# SCH_protopanda_v10.net
KiCad netlist of a schematic drawn in EasyEDA
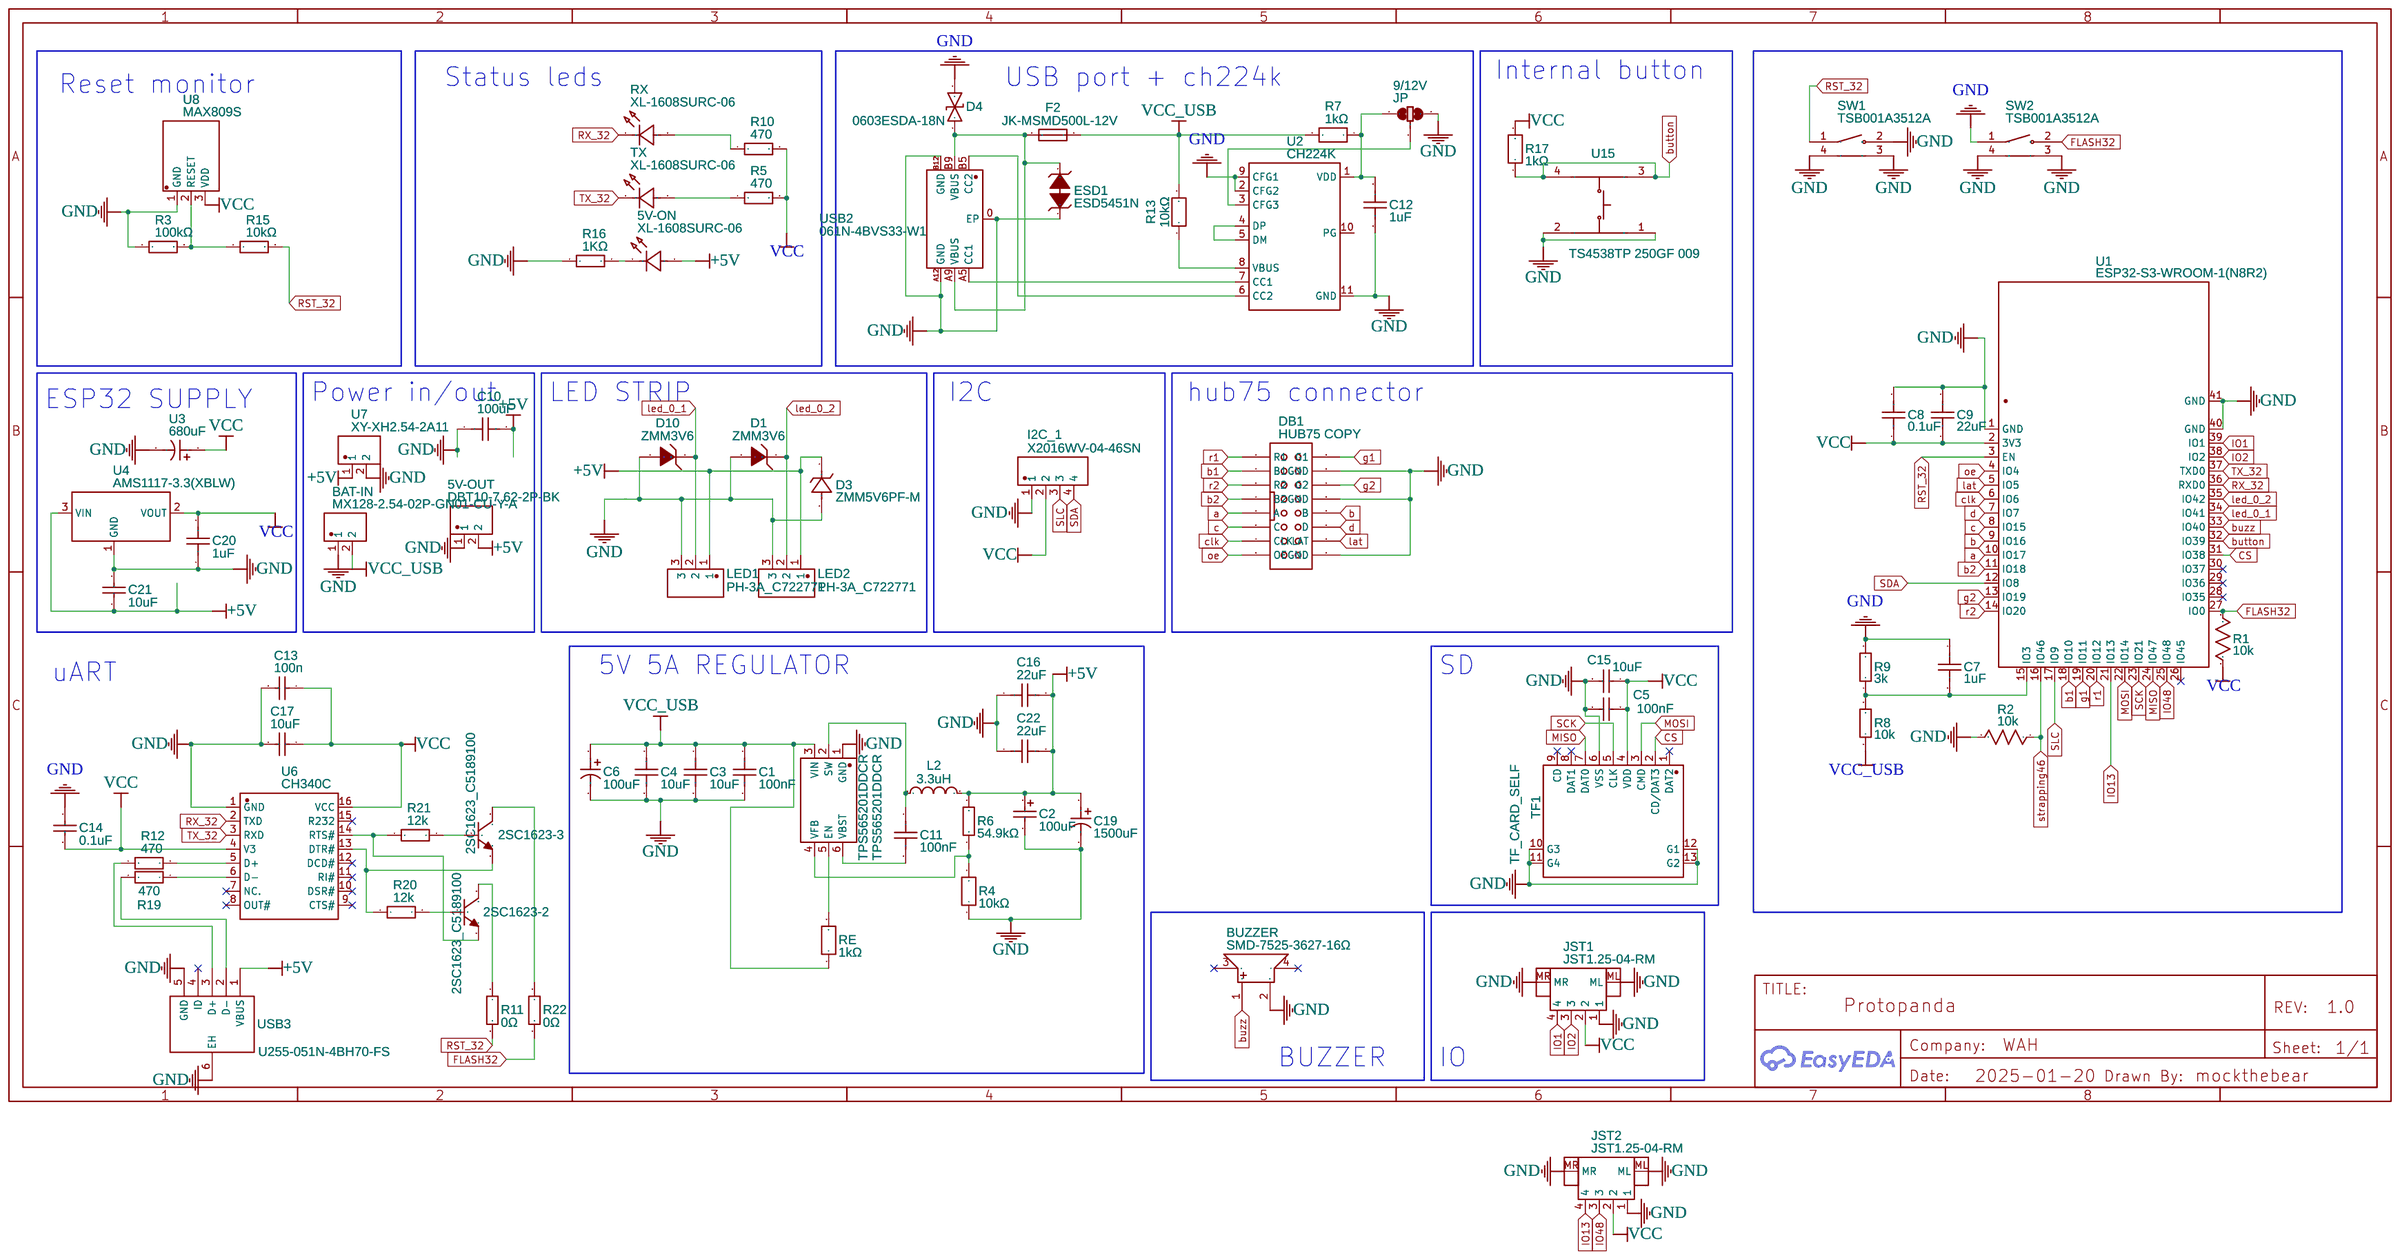
[diagram p0: schematic sheet]

(export (version "E")
  (design (tool "Eeschema 10.0.6"))
  (components
    (comp (ref "2SC1623-2")
      (value "2SC1623_C5189100")
      (fields (field (name "Manufacturer Part") "2SC1623") (field (name "Manufacturer") "HXY MOSFET(华轩阳电子)"))
      (libsource (lib "") (part "2SC1623_C5189100"))
    )
    (comp (ref "2SC1623-3")
      (value "2SC1623_C5189100")
      (fields (field (name "Manufacturer Part") "2SC1623") (field (name "Manufacturer") "HXY MOSFET(华轩阳电子)"))
      (libsource (lib "") (part "2SC1623_C5189100"))
    )
    (comp (ref "5V-ON")
      (value "XL-1608SURC-06")
      (fields (field (name "Manufacturer") "XINGLIGHT(成兴光)"))
      (libsource (lib "") (part "XL-1608SURC-06_2"))
    )
    (comp (ref "5V-OUT")
      (value "DBT10-7.62-2P-BK")
      (fields
        (field (name "Manufacturer Part") "DBT10-7.62-2P-BK-P")
        (field (name "Manufacturer") "DIBO(地博电气)")
      )
      (libsource (lib "") (part "DBT10-7.62-2P-BK"))
    )
    (comp (ref "9/12V") (value "JP") (libsource (lib "") (part "JUMPER-PAD-3-NOFULL_BOX_SILK")))
    (comp (ref "BAT-IN")
      (value "MX128-2.54-02P-GN01-CU-Y-A")
      (fields
        (field (name "Manufacturer Part") "MX128-2.54-02P-GN01-Cu-Y-A")
        (field (name "Manufacturer") "MAX(迈旭)")
      )
      (libsource (lib "") (part "MX128-2.54-02P-GN01-CU-Y-A"))
    )
    (comp (ref "BUZZER")
      (value "SMD-7525-3627-16Ω")
      (fields (field (name "Manufacturer") "S&S(海旭)"))
      (libsource (lib "") (part "SMD-7525-3627-16Ω"))
    )
    (comp (ref "C1")
      (value "100nF")
      (fields (field (name "Manufacturer Part") "CC0603CRNPO9BN5R1") (field (name "Manufacturer") "YAGEO"))
      (libsource (lib "") (part "CC0603CRNPO9BN5R1"))
    )
    (comp (ref "C2")
      (value "100uF")
      (fields
        (field (name "Manufacturer Part") "T490A107M006ATE800")
        (field (name "Manufacturer") "KEMET(基美)")
      )
      (libsource (lib "") (part "T490A107M006ATE800"))
    )
    (comp (ref "C3")
      (value "10uF")
      (fields (field (name "Manufacturer Part") "CC0603CRNPO9BN5R1") (field (name "Manufacturer") "YAGEO"))
      (libsource (lib "") (part "CC0603CRNPO9BN5R1"))
    )
    (comp (ref "C4")
      (value "10uF")
      (fields (field (name "Manufacturer Part") "CC0603CRNPO9BN5R1") (field (name "Manufacturer") "YAGEO"))
      (libsource (lib "") (part "CC0603CRNPO9BN5R1"))
    )
    (comp (ref "C5")
      (value "100nF")
      (fields (field (name "Manufacturer Part") "C0603X104K101T") (field (name "Manufacturer") "HEC"))
      (libsource (lib "") (part "C0603X104K101T"))
    )
    (comp (ref "C6")
      (value "100uF")
      (fields
        (field (name "Manufacturer Part") "RVT100UF25V67RV0011")
        (field (name "Manufacturer") "KNSCHA(科尼盛)")
      )
      (libsource (lib "") (part "RVT100UF25V67RV0011"))
    )
    (comp (ref "C7")
      (value "1uF")
      (fields
        (field (name "Manufacturer Part") "CS1608X7R105K250NRB")
        (field (name "Manufacturer") "Samwha Capacitor")
      )
      (libsource (lib "") (part "CS1608X7R105K250NRB_1"))
    )
    (comp (ref "C8")
      (value "0.1uF")
      (fields
        (field (name "Manufacturer Part") "0603BB104K500NGT")
        (field (name "Manufacturer") "Knowles(楼氏)")
      )
      (libsource (lib "") (part "0603BB104K500NGT"))
    )
    (comp (ref "C9")
      (value "22uF")
      (fields
        (field (name "Manufacturer Part") "GRM188R61A226ME15D")
        (field (name "Manufacturer") "muRata(村田)")
      )
      (libsource (lib "") (part "GRM188R61A226ME15D"))
    )
    (comp (ref "C10")
      (value "100uF")
      (fields
        (field (name "Manufacturer Part") "TCC1206X5R107M6R3HT")
        (field (name "Manufacturer") "CCTC(三环)")
      )
      (libsource (lib "") (part "TCC1206X5R107M6R3HT"))
    )
    (comp (ref "C11")
      (value "100nF")
      (fields (field (name "Manufacturer Part") "CC0603CRNPO9BN5R1") (field (name "Manufacturer") "YAGEO"))
      (libsource (lib "") (part "CC0603CRNPO9BN5R1"))
    )
    (comp (ref "C12")
      (value "1uF")
      (fields (field (name "Manufacturer Part") "CC0603CRNPO9BN5R1") (field (name "Manufacturer") "YAGEO"))
      (libsource (lib "") (part "CC0603CRNPO9BN5R1"))
    )
    (comp (ref "C13")
      (value "100n")
      (fields (field (name "Manufacturer Part") "CC0603KRX5R5BB106") (field (name "Manufacturer") "YAGEO"))
      (libsource (lib "") (part "CC0603KRX5R5BB106_1"))
    )
    (comp (ref "C14")
      (value "0.1uF")
      (fields (field (name "Manufacturer Part") "CC0603KRX5R5BB106") (field (name "Manufacturer") "YAGEO"))
      (libsource (lib "") (part "CC0603KRX5R5BB106"))
    )
    (comp (ref "C15")
      (value "10uF")
      (fields (field (name "Manufacturer Part") "CC0603MRX5R6BB106") (field (name "Manufacturer") "YAGEO"))
      (libsource (lib "") (part "CC0603MRX5R6BB106_1"))
    )
    (comp (ref "C16") (value "22uF") (libsource (lib "") (part "C_0805_US")))
    (comp (ref "C17")
      (value "10uF")
      (fields (field (name "Manufacturer Part") "CC0603KRX5R5BB106") (field (name "Manufacturer") "YAGEO"))
      (libsource (lib "") (part "CC0603KRX5R5BB106_1"))
    )
    (comp (ref "C19")
      (value "1500uF")
      (fields (field (name "Manufacturer Part") "189RV0022") (field (name "Manufacturer") "KNSCHA(科尼盛)"))
      (libsource (lib "") (part "189RV0022"))
    )
    (comp (ref "C20")
      (value "1uF")
      (fields
        (field (name "Manufacturer Part") "CS1608X7R105K250NRB")
        (field (name "Manufacturer") "Samwha Capacitor")
      )
      (libsource (lib "") (part "CS1608X7R105K250NRB"))
    )
    (comp (ref "C21")
      (value "10uF")
      (fields (field (name "Manufacturer Part") "CC0603MRX5R6BB106") (field (name "Manufacturer") "YAGEO"))
      (libsource (lib "") (part "CC0603MRX5R6BB106"))
    )
    (comp (ref "C22") (value "22uF") (libsource (lib "") (part "C_0805_US")))
    (comp (ref "D1")
      (value "ZMM3V6")
      (fields (field (name "Manufacturer Part") "ZMM3V6-M") (field (name "Manufacturer") "ST(先科)"))
      (libsource (lib "") (part "ZMM3V6"))
    )
    (comp (ref "D3")
      (value "ZMM5V6PF-M")
      (fields (field (name "Manufacturer") "ST(先科)"))
      (libsource (lib "") (part "ZMM5V6PF-M"))
    )
    (comp (ref "D4")
      (value "0603ESDA-18N")
      (fields (field (name "Manufacturer") "BORN(伯恩半导体)"))
      (libsource (lib "") (part "0603ESDA-18N"))
    )
    (comp (ref "D10")
      (value "ZMM3V6")
      (fields (field (name "Manufacturer Part") "ZMM3V6-M") (field (name "Manufacturer") "ST(先科)"))
      (libsource (lib "") (part "ZMM3V6"))
    )
    (comp (ref "DB1") (value "HUB75 COPY") (libsource (lib "") (part "HUB75 COPY")))
    (comp (ref "ESD1")
      (value "ESD5451N")
      (fields (field (name "Manufacturer") "UMW(广东友台半导体)"))
      (libsource (lib "") (part "ESD5451N"))
    )
    (comp (ref "F2")
      (value "JK-MSMD500L-12V")
      (fields (field (name "Manufacturer") "JK(金科)"))
      (libsource (lib "") (part "JK-MSMD500L-12V"))
    )
    (comp (ref "I2C_1")
      (value "X2016WV-04-46SN")
      (fields (field (name "Manufacturer") "XKB Connectivity(中国星坤)"))
      (libsource (lib "") (part "X2016WV-04-46SN"))
    )
    (comp (ref "JST1") (value "JST1.25-04-RM") (libsource (lib "") (part "JST1.25-04-RM")))
    (comp (ref "JST2") (value "JST1.25-04-RM") (libsource (lib "") (part "JST1.25-04-RM")))
    (comp (ref "L2")
      (value "3.3uH")
      (fields
        (field (name "Manufacturer Part") "PSPMAA1040H-3R3M-ANP")
        (field (name "Manufacturer") "PROD(谱罗德)")
      )
      (libsource (lib "") (part "PSPMAA1040H-3R3M-ANP"))
    )
    (comp (ref "LED1")
      (value "PH-3A_C722771")
      (fields (field (name "Manufacturer Part") "PH-3A") (field (name "Manufacturer") "CAX(创都)"))
      (libsource (lib "") (part "PH-3A_C722771"))
    )
    (comp (ref "LED2")
      (value "PH-3A_C722771")
      (fields (field (name "Manufacturer Part") "PH-3A") (field (name "Manufacturer") "CAX(创都)"))
      (libsource (lib "") (part "PH-3A_C722771"))
    )
    (comp (ref "R1") (value "10k") (libsource (lib "") (part "R_0603_US_1")))
    (comp (ref "R2") (value "10k") (libsource (lib "") (part "R_0603_US")))
    (comp (ref "R3")
      (value "100kΩ")
      (fields
        (field (name "Manufacturer Part") "PTFR0603B10K0P9")
        (field (name "Manufacturer") "ResistorToday")
      )
      (libsource (lib "") (part "PTFR0603B10K0P9"))
    )
    (comp (ref "R4")
      (value "10kΩ")
      (fields (field (name "Manufacturer Part") "FRC0603F4992TS") (field (name "Manufacturer") "FOJAN(富捷)"))
      (libsource (lib "") (part "FRC0603F4992TS"))
    )
    (comp (ref "R5")
      (value "470")
      (fields (field (name "Manufacturer Part") "CR0603FA56R0G") (field (name "Manufacturer") "LIZ"))
      (libsource (lib "") (part "CR0603FA56R0G"))
    )
    (comp (ref "R6")
      (value "54.9kΩ")
      (fields
        (field (name "Manufacturer Part") "RCT03365KFLF")
        (field (name "Manufacturer") "Hong Kong Resistors")
      )
      (libsource (lib "") (part "RCT03365KFLF"))
    )
    (comp (ref "R7")
      (value "1kΩ")
      (fields (field (name "Manufacturer Part") "FRC0603F4992TS") (field (name "Manufacturer") "FOJAN(富捷)"))
      (libsource (lib "") (part "FRC0603F4992TS_2"))
    )
    (comp (ref "R8")
      (value "10k")
      (fields (field (name "Manufacturer Part") "CR0603FA56R0G") (field (name "Manufacturer") "LIZ"))
      (libsource (lib "") (part "CR0603FA56R0G_1"))
    )
    (comp (ref "R9")
      (value "3k")
      (fields (field (name "Manufacturer Part") "CR0603FA56R0G") (field (name "Manufacturer") "LIZ"))
      (libsource (lib "") (part "CR0603FA56R0G_1"))
    )
    (comp (ref "R10")
      (value "470")
      (fields (field (name "Manufacturer Part") "CR0603FA56R0G") (field (name "Manufacturer") "LIZ"))
      (libsource (lib "") (part "CR0603FA56R0G"))
    )
    (comp (ref "R11")
      (value "0Ω")
      (fields
        (field (name "Manufacturer Part") "AECR0603F100RK9")
        (field (name "Manufacturer") "ResistorToday")
      )
      (libsource (lib "") (part "AECR0603F100RK9_1"))
    )
    (comp (ref "R12")
      (value "470")
      (fields (field (name "Manufacturer Part") "CR0603FA56R0G") (field (name "Manufacturer") "LIZ"))
      (libsource (lib "") (part "CR0603FA56R0G"))
    )
    (comp (ref "R13")
      (value "10kΩ")
      (fields (field (name "Manufacturer Part") "FRC0603F4992TS") (field (name "Manufacturer") "FOJAN(富捷)"))
      (libsource (lib "") (part "FRC0603F4992TS"))
    )
    (comp (ref "R15")
      (value "10kΩ")
      (fields
        (field (name "Manufacturer Part") "PTFR0603B10K0P9")
        (field (name "Manufacturer") "ResistorToday")
      )
      (libsource (lib "") (part "PTFR0603B10K0P9"))
    )
    (comp (ref "R16")
      (value "1KΩ")
      (fields (field (name "Manufacturer Part") "CR0603FA56R0G") (field (name "Manufacturer") "LIZ"))
      (libsource (lib "") (part "CR0603FA56R0G"))
    )
    (comp (ref "R17")
      (value "1kΩ")
      (fields (field (name "Manufacturer Part") "FRC0603F4992TS") (field (name "Manufacturer") "FOJAN(富捷)"))
      (libsource (lib "") (part "FRC0603F4992TS"))
    )
    (comp (ref "R19")
      (value "470")
      (fields (field (name "Manufacturer Part") "CR0603FA56R0G") (field (name "Manufacturer") "LIZ"))
      (libsource (lib "") (part "CR0603FA56R0G_2"))
    )
    (comp (ref "R20")
      (value "12k")
      (fields (field (name "Manufacturer Part") "CR0603FA56R0G") (field (name "Manufacturer") "LIZ"))
      (libsource (lib "") (part "CR0603FA56R0G"))
    )
    (comp (ref "R21")
      (value "12k")
      (fields (field (name "Manufacturer Part") "CR0603FA56R0G") (field (name "Manufacturer") "LIZ"))
      (libsource (lib "") (part "CR0603FA56R0G"))
    )
    (comp (ref "R22")
      (value "0Ω")
      (fields
        (field (name "Manufacturer Part") "AECR0603F100RK9")
        (field (name "Manufacturer") "ResistorToday")
      )
      (libsource (lib "") (part "AECR0603F100RK9"))
    )
    (comp (ref "RE")
      (value "1kΩ")
      (fields (field (name "Manufacturer Part") "FRC0603F4992TS") (field (name "Manufacturer") "FOJAN(富捷)"))
      (libsource (lib "") (part "FRC0603F4992TS_1"))
    )
    (comp (ref "RX")
      (value "XL-1608SURC-06")
      (fields (field (name "Manufacturer") "XINGLIGHT(成兴光)"))
      (libsource (lib "") (part "XL-1608SURC-06_1"))
    )
    (comp (ref "SW1")
      (value "TSB001A3512A")
      (fields (field (name "Manufacturer") "BZCN(博众电气)"))
      (libsource (lib "") (part "TSB001A3512A"))
    )
    (comp (ref "SW2")
      (value "TSB001A3512A")
      (fields (field (name "Manufacturer") "BZCN(博众电气)"))
      (libsource (lib "") (part "TSB001A3512A"))
    )
    (comp (ref "TF1") (value "TF_CARD_SELF") (libsource (lib "") (part "TF_CARD_SELF")))
    (comp (ref "TPS565201DDCR")
      (value "TPS565201DDCR")
      (fields (field (name "Manufacturer") "TI(德州仪器)"))
      (libsource (lib "") (part "TPS565201DDCR"))
    )
    (comp (ref "TX")
      (value "XL-1608SURC-06")
      (fields (field (name "Manufacturer") "XINGLIGHT(成兴光)"))
      (libsource (lib "") (part "XL-1608SURC-06"))
    )
    (comp (ref "U1")
      (value "ESP32-S3-WROOM-1(N8R2)")
      (fields
        (field (name "Manufacturer Part") "ESP32-S3-WROOM-1-N8R2")
        (field (name "Manufacturer") "ESPRESSIF(乐鑫)")
      )
      (libsource (lib "") (part "ESP32-S3-WROOM-1(N8R2)"))
    )
    (comp (ref "U2")
      (value "CH224K")
      (fields (field (name "Manufacturer") "WCH(南京沁恒)"))
      (libsource (lib "") (part "CH224K"))
    )
    (comp (ref "U3")
      (value "680uF")
      (fields (field (name "Manufacturer Part") "189RV0015") (field (name "Manufacturer") "KNSCHA(科尼盛)"))
      (libsource (lib "") (part "189RV0015"))
    )
    (comp (ref "U4")
      (value "AMS1117-3.3(XBLW)")
      (fields (field (name "Manufacturer") "XBLW(芯伯乐)"))
      (libsource (lib "") (part "AMS1117-3.3(XBLW)"))
    )
    (comp (ref "U6")
      (value "CH340C")
      (fields (field (name "Manufacturer") "WCH(南京沁恒)"))
      (libsource (lib "") (part "CH340C"))
    )
    (comp (ref "U7")
      (value "XY-XH2.54-2A11")
      (fields (field (name "Manufacturer") "XYECONN(辛译)"))
      (libsource (lib "") (part "XY-XH2.54-2A11"))
    )
    (comp (ref "U8")
      (value "MAX809S")
      (fields (field (name "Manufacturer") "UMW(广东友台半导体)"))
      (libsource (lib "") (part "MAX809S"))
    )
    (comp (ref "U15")
      (value "TS4538TP 250GF 009")
      (fields
        (field (name "Manufacturer Part") "TS4538TP 250gf 009")
        (field (name "Manufacturer") "SHOU HAN(首韩)")
      )
      (libsource (lib "") (part "TS4538TP 250GF 009"))
    )
    (comp (ref "USB2")
      (value "061N-4BVS33-W1")
      (fields (field (name "Manufacturer") "HanElectricity(瀚源)"))
      (libsource (lib "") (part "061N-4BVS33-W1"))
    )
    (comp (ref "USB3")
      (value "U255-051N-4BH70-FS")
      (fields (field (name "Manufacturer") "XKB Enterprise"))
      (libsource (lib "") (part "U255-051N-4BH70-FS"))
    )
  )
  (nets
    (net (code "1") (name "+5V") (class "Default")
      (node (ref "5V-ON") (pin "2") (pinfunction "A_2") (pintype "unspecified"))
      (node (ref "5V-OUT") (pin "2") (pinfunction "2_2") (pintype "unspecified"))
      (node (ref "C10") (pin "2") (pinfunction "2_2") (pintype "unspecified"))
      (node (ref "C16") (pin "2") (pinfunction "2_2") (pintype "unspecified"))
      (node (ref "C19") (pin "1") (pinfunction "1_1") (pintype "input"))
      (node (ref "C2") (pin "1") (pinfunction "1_1") (pintype "input"))
      (node (ref "C21") (pin "2") (pinfunction "2_2") (pintype "input"))
      (node (ref "C22") (pin "2") (pinfunction "2_2") (pintype "unspecified"))
      (node (ref "D3") (pin "1") (pinfunction "C_1") (pintype "unspecified"))
      (node (ref "L2") (pin "2") (pinfunction "2_2") (pintype "unspecified"))
      (node (ref "LED1") (pin "1") (pinfunction "1_1") (pintype "unspecified"))
      (node (ref "LED2") (pin "1") (pinfunction "1_1") (pintype "unspecified"))
      (node (ref "R6") (pin "2") (pinfunction "2_2") (pintype "unspecified"))
      (node (ref "U4") (pin "3") (pinfunction "VIN_3") (pintype "unspecified"))
      (node (ref "U7") (pin "1") (pinfunction "1_1") (pintype "unspecified"))
      (node (ref "USB3") (pin "1") (pinfunction "VBUS_1") (pintype "unspecified"))
    )
    (net (code "2") (name "CS") (class "Default")
      (node (ref "TF1") (pin "2") (pinfunction "CD/DAT3_2") (pintype "unspecified"))
      (node (ref "U1") (pin "31") (pinfunction "IO38_31") (pintype "unspecified"))
    )
    (net (code "3") (name "FLASH32") (class "Default")
      (node (ref "R1") (pin "2") (pinfunction "2_2") (pintype "unspecified"))
      (node (ref "R22") (pin "1") (pinfunction "1_1") (pintype "unspecified"))
      (node (ref "SW2") (pin "2") (pinfunction "2_2") (pintype "unspecified"))
      (node (ref "U1") (pin "27") (pinfunction "IO0_27") (pintype "unspecified"))
    )
    (net (code "4") (name "GND") (class "Default")
      (node (ref "5V-OUT") (pin "1") (pinfunction "1_1") (pintype "unspecified"))
      (node (ref "9/12V") (pin "3") (pinfunction "3_3") (pintype "unspecified"))
      (node (ref "BAT-IN") (pin "1") (pinfunction "1_1") (pintype "unspecified"))
      (node (ref "BUZZER") (pin "2") (pinfunction "2_2") (pintype "unspecified"))
      (node (ref "C1") (pin "2") (pinfunction "2_2") (pintype "unspecified"))
      (node (ref "C10") (pin "1") (pinfunction "1_1") (pintype "unspecified"))
      (node (ref "C12") (pin "2") (pinfunction "2_2") (pintype "unspecified"))
      (node (ref "C13") (pin "2") (pinfunction "2_2") (pintype "input"))
      (node (ref "C14") (pin "1") (pinfunction "1_1") (pintype "input"))
      (node (ref "C15") (pin "2") (pinfunction "2_2") (pintype "input"))
      (node (ref "C16") (pin "1") (pinfunction "1_1") (pintype "unspecified"))
      (node (ref "C17") (pin "2") (pinfunction "2_2") (pintype "input"))
      (node (ref "C19") (pin "2") (pinfunction "2_2") (pintype "input"))
      (node (ref "C2") (pin "2") (pinfunction "2_2") (pintype "input"))
      (node (ref "C20") (pin "1") (pinfunction "1_1") (pintype "unspecified"))
      (node (ref "C21") (pin "1") (pinfunction "1_1") (pintype "input"))
      (node (ref "C22") (pin "1") (pinfunction "1_1") (pintype "unspecified"))
      (node (ref "C3") (pin "2") (pinfunction "2_2") (pintype "unspecified"))
      (node (ref "C4") (pin "2") (pinfunction "2_2") (pintype "unspecified"))
      (node (ref "C5") (pin "1") (pinfunction "1_1") (pintype "input"))
      (node (ref "C6") (pin "2") (pinfunction "2_2") (pintype "input"))
      (node (ref "C7") (pin "1") (pinfunction "1_1") (pintype "unspecified"))
      (node (ref "C8") (pin "2") (pinfunction "2_2") (pintype "unspecified"))
      (node (ref "C9") (pin "1") (pinfunction "1_1") (pintype "unspecified"))
      (node (ref "D1") (pin "2") (pinfunction "A_2") (pintype "unspecified"))
      (node (ref "D10") (pin "2") (pinfunction "A_2") (pintype "unspecified"))
      (node (ref "D3") (pin "2") (pinfunction "A_2") (pintype "unspecified"))
      (node (ref "D4") (pin "2") (pinfunction "2_2") (pintype "unspecified"))
      (node (ref "DB1") (pin "13") (pinfunction "GND_13") (pintype "unspecified"))
      (node (ref "DB1") (pin "15") (pinfunction "GND_15") (pintype "unspecified"))
      (node (ref "DB1") (pin "9") (pinfunction "GND_9") (pintype "unspecified"))
      (node (ref "ESD1") (pin "1") (pinfunction "1_1") (pintype "unspecified"))
      (node (ref "I2C_1") (pin "1") (pinfunction "1_1") (pintype "unspecified"))
      (node (ref "JST1") (pin "1") (pinfunction "1_1") (pintype "unspecified"))
      (node (ref "JST1") (pin "ML") (pinfunction "ML_ML") (pintype "unspecified"))
      (node (ref "JST1") (pin "MR") (pinfunction "MR_MR") (pintype "unspecified"))
      (node (ref "JST2") (pin "1") (pinfunction "1_1") (pintype "unspecified"))
      (node (ref "JST2") (pin "ML") (pinfunction "ML_ML") (pintype "unspecified"))
      (node (ref "JST2") (pin "MR") (pinfunction "MR_MR") (pintype "unspecified"))
      (node (ref "LED1") (pin "3") (pinfunction "3_3") (pintype "unspecified"))
      (node (ref "LED2") (pin "3") (pinfunction "3_3") (pintype "unspecified"))
      (node (ref "R16") (pin "1") (pinfunction "1_1") (pintype "input"))
      (node (ref "R2") (pin "2") (pinfunction "2_2") (pintype "unspecified"))
      (node (ref "R3") (pin "1") (pinfunction "1_1") (pintype "unspecified"))
      (node (ref "R4") (pin "1") (pinfunction "1_1") (pintype "unspecified"))
      (node (ref "R9") (pin "2") (pinfunction "2_2") (pintype "input"))
      (node (ref "SW1") (pin "2") (pinfunction "2_2") (pintype "unspecified"))
      (node (ref "SW1") (pin "3") (pinfunction "3_3") (pintype "unspecified"))
      (node (ref "SW1") (pin "4") (pinfunction "4_4") (pintype "unspecified"))
      (node (ref "SW2") (pin "1") (pinfunction "1_1") (pintype "unspecified"))
      (node (ref "SW2") (pin "3") (pinfunction "3_3") (pintype "unspecified"))
      (node (ref "SW2") (pin "4") (pinfunction "4_4") (pintype "unspecified"))
      (node (ref "TF1") (pin "10") (pinfunction "G3_10") (pintype "unspecified"))
      (node (ref "TF1") (pin "11") (pinfunction "G4_11") (pintype "unspecified"))
      (node (ref "TF1") (pin "12") (pinfunction "G1_12") (pintype "unspecified"))
      (node (ref "TF1") (pin "13") (pinfunction "G2_13") (pintype "unspecified"))
      (node (ref "TF1") (pin "6") (pinfunction "VSS_6") (pintype "unspecified"))
      (node (ref "TPS565201DDCR") (pin "1") (pinfunction "GND_1") (pintype "unspecified"))
      (node (ref "U1") (pin "1") (pinfunction "GND_1") (pintype "unspecified"))
      (node (ref "U1") (pin "40") (pinfunction "GND_40") (pintype "unspecified"))
      (node (ref "U1") (pin "41") (pinfunction "GND_41") (pintype "unspecified"))
      (node (ref "U15") (pin "1") (pinfunction "1_1") (pintype "unspecified"))
      (node (ref "U15") (pin "2") (pinfunction "2_2") (pintype "unspecified"))
      (node (ref "U2") (pin "11") (pinfunction "GND_11") (pintype "unspecified"))
      (node (ref "U2") (pin "2") (pinfunction "CFG2_2") (pintype "unspecified"))
      (node (ref "U2") (pin "9") (pinfunction "CFG1_9") (pintype "unspecified"))
      (node (ref "U3") (pin "2") (pinfunction "2_2") (pintype "input"))
      (node (ref "U4") (pin "1") (pinfunction "GND_1") (pintype "unspecified"))
      (node (ref "U6") (pin "1") (pinfunction "GND_1") (pintype "unspecified"))
      (node (ref "U7") (pin "2") (pinfunction "2_2") (pintype "unspecified"))
      (node (ref "U8") (pin "1") (pinfunction "GND_1") (pintype "unspecified"))
      (node (ref "USB2") (pin "0") (pinfunction "EP_0") (pintype "unspecified"))
      (node (ref "USB2") (pin "A12") (pinfunction "GND_A12") (pintype "unspecified"))
      (node (ref "USB2") (pin "B12") (pinfunction "GND_B12") (pintype "unspecified"))
      (node (ref "USB3") (pin "5") (pinfunction "GND_5") (pintype "unspecified"))
      (node (ref "USB3") (pin "6") (pinfunction "EH_6") (pintype "unspecified"))
    )
    (net (code "5") (name "IO1") (class "Default")
      (node (ref "JST1") (pin "4") (pinfunction "4_4") (pintype "unspecified"))
      (node (ref "U1") (pin "39") (pinfunction "IO1_39") (pintype "unspecified"))
    )
    (net (code "6") (name "IO2") (class "Default")
      (node (ref "JST1") (pin "3") (pinfunction "3_3") (pintype "unspecified"))
      (node (ref "U1") (pin "38") (pinfunction "IO2_38") (pintype "unspecified"))
    )
    (net (code "7") (name "IO13") (class "Default")
      (node (ref "JST2") (pin "4") (pinfunction "4_4") (pintype "unspecified"))
      (node (ref "U1") (pin "21") (pinfunction "IO13_21") (pintype "unspecified"))
    )
    (net (code "8") (name "IO48") (class "Default")
      (node (ref "JST2") (pin "3") (pinfunction "3_3") (pintype "unspecified"))
      (node (ref "U1") (pin "25") (pinfunction "IO48_25") (pintype "unspecified"))
    )
    (net (code "9") (name "MISO") (class "Default")
      (node (ref "TF1") (pin "7") (pinfunction "DAT0_7") (pintype "unspecified"))
      (node (ref "U1") (pin "24") (pinfunction "IO47_24") (pintype "unspecified"))
    )
    (net (code "10") (name "MOSI") (class "Default")
      (node (ref "TF1") (pin "3") (pinfunction "CMD_3") (pintype "unspecified"))
      (node (ref "U1") (pin "22") (pinfunction "IO14_22") (pintype "unspecified"))
    )
    (net (code "11") (name "Net-(2SC1623-2-B)") (class "Default")
      (node (ref "2SC1623-2") (pin "1") (pinfunction "B_1") (pintype "input"))
      (node (ref "R20") (pin "2") (pinfunction "2_2") (pintype "input"))
    )
    (net (code "12") (name "Net-(2SC1623-2-C)") (class "Default")
      (node (ref "2SC1623-2") (pin "3") (pinfunction "C_3") (pintype "input"))
      (node (ref "R11") (pin "1") (pinfunction "1_1") (pintype "unspecified"))
    )
    (net (code "13") (name "Net-(2SC1623-2-E)") (class "Default")
      (node (ref "2SC1623-2") (pin "2") (pinfunction "E_2") (pintype "input"))
      (node (ref "R21") (pin "1") (pinfunction "1_1") (pintype "input"))
      (node (ref "U6") (pin "14") (pinfunction "RTS#_14") (pintype "unspecified"))
    )
    (net (code "14") (name "Net-(2SC1623-3-B)") (class "Default")
      (node (ref "2SC1623-3") (pin "1") (pinfunction "B_1") (pintype "input"))
      (node (ref "R21") (pin "2") (pinfunction "2_2") (pintype "input"))
    )
    (net (code "15") (name "Net-(2SC1623-3-C)") (class "Default")
      (node (ref "2SC1623-3") (pin "3") (pinfunction "C_3") (pintype "input"))
      (node (ref "R22") (pin "2") (pinfunction "2_2") (pintype "unspecified"))
    )
    (net (code "16") (name "Net-(2SC1623-3-E)") (class "Default")
      (node (ref "2SC1623-3") (pin "2") (pinfunction "E_2") (pintype "input"))
      (node (ref "R20") (pin "1") (pinfunction "1_1") (pintype "input"))
      (node (ref "U6") (pin "13") (pinfunction "DTR#_13") (pintype "unspecified"))
    )
    (net (code "17") (name "Net-(5V-ON-K)") (class "Default")
      (node (ref "5V-ON") (pin "1") (pinfunction "K_1") (pintype "unspecified"))
      (node (ref "R16") (pin "2") (pinfunction "2_2") (pintype "input"))
    )
    (net (code "18") (name "Net-(D4-Pad1)") (class "Default")
      (node (ref "D4") (pin "1") (pinfunction "1_1") (pintype "unspecified"))
      (node (ref "ESD1") (pin "2") (pinfunction "2_2") (pintype "unspecified"))
      (node (ref "F2") (pin "2") (pinfunction "2_2") (pintype "unspecified"))
      (node (ref "USB2") (pin "A9") (pinfunction "VBUS_A9") (pintype "unspecified"))
      (node (ref "USB2") (pin "B9") (pinfunction "VBUS_B9") (pintype "unspecified"))
    )
    (net (code "19") (name "Net-(RX-A)") (class "Default")
      (node (ref "R10") (pin "1") (pinfunction "1_1") (pintype "input"))
      (node (ref "RX") (pin "2") (pinfunction "A_2") (pintype "unspecified"))
    )
    (net (code "20") (name "Net-(TPS565201DDCR-EN)") (class "Default")
      (node (ref "RE") (pin "2") (pinfunction "2_2") (pintype "unspecified"))
      (node (ref "TPS565201DDCR") (pin "5") (pinfunction "EN_5") (pintype "unspecified"))
    )
    (net (code "21") (name "Net-(TPS565201DDCR-SW)") (class "Default")
      (node (ref "C11") (pin "1") (pinfunction "1_1") (pintype "unspecified"))
      (node (ref "L2") (pin "1") (pinfunction "1_1") (pintype "unspecified"))
      (node (ref "TPS565201DDCR") (pin "2") (pinfunction "SW_2") (pintype "unspecified"))
    )
    (net (code "22") (name "Net-(TPS565201DDCR-VBST)") (class "Default")
      (node (ref "C11") (pin "2") (pinfunction "2_2") (pintype "unspecified"))
      (node (ref "TPS565201DDCR") (pin "6") (pinfunction "VBST_6") (pintype "unspecified"))
    )
    (net (code "23") (name "Net-(TPS565201DDCR-VFB)") (class "Default")
      (node (ref "R4") (pin "2") (pinfunction "2_2") (pintype "unspecified"))
      (node (ref "R6") (pin "1") (pinfunction "1_1") (pintype "unspecified"))
      (node (ref "TPS565201DDCR") (pin "4") (pinfunction "VFB_4") (pintype "unspecified"))
    )
    (net (code "24") (name "Net-(TX-A)") (class "Default")
      (node (ref "R5") (pin "1") (pinfunction "1_1") (pintype "input"))
      (node (ref "TX") (pin "2") (pinfunction "A_2") (pintype "unspecified"))
    )
    (net (code "25") (name "Net-(U1-IO3)") (class "Default")
      (node (ref "C7") (pin "2") (pinfunction "2_2") (pintype "unspecified"))
      (node (ref "R8") (pin "2") (pinfunction "2_2") (pintype "input"))
      (node (ref "R9") (pin "1") (pinfunction "1_1") (pintype "input"))
      (node (ref "U1") (pin "15") (pinfunction "IO3_15") (pintype "unspecified"))
    )
    (net (code "26") (name "Net-(U2-CC1)") (class "Default")
      (node (ref "U2") (pin "7") (pinfunction "CC1_7") (pintype "unspecified"))
      (node (ref "USB2") (pin "A5") (pinfunction "CC1_A5") (pintype "unspecified"))
    )
    (net (code "27") (name "Net-(U2-CC2)") (class "Default")
      (node (ref "U2") (pin "6") (pinfunction "CC2_6") (pintype "unspecified"))
      (node (ref "USB2") (pin "B5") (pinfunction "CC2_B5") (pintype "unspecified"))
    )
    (net (code "28") (name "Net-(U2-CFG3)") (class "Default")
      (node (ref "9/12V") (pin "2") (pinfunction "2_2") (pintype "unspecified"))
      (node (ref "U2") (pin "3") (pinfunction "CFG3_3") (pintype "unspecified"))
    )
    (net (code "29") (name "Net-(U2-DM)") (class "Default")
      (node (ref "U2") (pin "4") (pinfunction "DP_4") (pintype "unspecified"))
      (node (ref "U2") (pin "5") (pinfunction "DM_5") (pintype "unspecified"))
    )
    (net (code "30") (name "Net-(U2-VBUS)") (class "Default")
      (node (ref "R13") (pin "1") (pinfunction "1_1") (pintype "unspecified"))
      (node (ref "U2") (pin "8") (pinfunction "VBUS_8") (pintype "unspecified"))
    )
    (net (code "31") (name "Net-(U2-VDD)") (class "Default")
      (node (ref "9/12V") (pin "1") (pinfunction "1_1") (pintype "unspecified"))
      (node (ref "C12") (pin "1") (pinfunction "1_1") (pintype "unspecified"))
      (node (ref "R7") (pin "1") (pinfunction "1_1") (pintype "unspecified"))
      (node (ref "U2") (pin "1") (pinfunction "VDD_1") (pintype "unspecified"))
    )
    (net (code "32") (name "Net-(U6-D+)") (class "Default")
      (node (ref "R12") (pin "2") (pinfunction "2_2") (pintype "input"))
      (node (ref "U6") (pin "5") (pinfunction "D+_5") (pintype "unspecified"))
    )
    (net (code "33") (name "Net-(U6-D-)") (class "Default")
      (node (ref "R19") (pin "1") (pinfunction "1_1") (pintype "input"))
      (node (ref "U6") (pin "6") (pinfunction "D-_6") (pintype "unspecified"))
    )
    (net (code "34") (name "Net-(U8-RESET)") (class "Default")
      (node (ref "R15") (pin "1") (pinfunction "1_1") (pintype "unspecified"))
      (node (ref "R3") (pin "2") (pinfunction "2_2") (pintype "unspecified"))
      (node (ref "U8") (pin "2") (pinfunction "RESET_2") (pintype "unspecified"))
    )
    (net (code "35") (name "Net-(USB3-D+)") (class "Default")
      (node (ref "R12") (pin "1") (pinfunction "1_1") (pintype "input"))
      (node (ref "USB3") (pin "3") (pinfunction "D+_3") (pintype "unspecified"))
    )
    (net (code "36") (name "Net-(USB3-D-)") (class "Default")
      (node (ref "R19") (pin "2") (pinfunction "2_2") (pintype "input"))
      (node (ref "USB3") (pin "2") (pinfunction "D-_2") (pintype "unspecified"))
    )
    (net (code "37") (name "RST_32") (class "Default")
      (node (ref "R11") (pin "2") (pinfunction "2_2") (pintype "unspecified"))
      (node (ref "R15") (pin "2") (pinfunction "2_2") (pintype "unspecified"))
      (node (ref "SW1") (pin "1") (pinfunction "1_1") (pintype "unspecified"))
      (node (ref "U1") (pin "3") (pinfunction "EN_3") (pintype "unspecified"))
    )
    (net (code "38") (name "RX_32") (class "Default")
      (node (ref "RX") (pin "1") (pinfunction "K_1") (pintype "unspecified"))
      (node (ref "U1") (pin "36") (pinfunction "RXD0_36") (pintype "unspecified"))
      (node (ref "U6") (pin "2") (pinfunction "TXD_2") (pintype "unspecified"))
    )
    (net (code "39") (name "SCK") (class "Default")
      (node (ref "TF1") (pin "5") (pinfunction "CLK_5") (pintype "unspecified"))
      (node (ref "U1") (pin "23") (pinfunction "IO21_23") (pintype "unspecified"))
    )
    (net (code "40") (name "SDA") (class "Default")
      (node (ref "I2C_1") (pin "4") (pinfunction "4_4") (pintype "unspecified"))
      (node (ref "U1") (pin "12") (pinfunction "IO8_12") (pintype "unspecified"))
    )
    (net (code "41") (name "SLC") (class "Default")
      (node (ref "I2C_1") (pin "3") (pinfunction "3_3") (pintype "unspecified"))
      (node (ref "U1") (pin "17") (pinfunction "IO9_17") (pintype "unspecified"))
    )
    (net (code "42") (name "TX_32") (class "Default")
      (node (ref "TX") (pin "1") (pinfunction "K_1") (pintype "unspecified"))
      (node (ref "U1") (pin "37") (pinfunction "TXD0_37") (pintype "unspecified"))
      (node (ref "U6") (pin "3") (pinfunction "RXD_3") (pintype "unspecified"))
    )
    (net (code "43") (name "VCC") (class "Default")
      (node (ref "C13") (pin "1") (pinfunction "1_1") (pintype "input"))
      (node (ref "C14") (pin "2") (pinfunction "2_2") (pintype "input"))
      (node (ref "C15") (pin "1") (pinfunction "1_1") (pintype "input"))
      (node (ref "C17") (pin "1") (pinfunction "1_1") (pintype "input"))
      (node (ref "C20") (pin "2") (pinfunction "2_2") (pintype "unspecified"))
      (node (ref "C5") (pin "2") (pinfunction "2_2") (pintype "input"))
      (node (ref "C8") (pin "1") (pinfunction "1_1") (pintype "unspecified"))
      (node (ref "C9") (pin "2") (pinfunction "2_2") (pintype "unspecified"))
      (node (ref "I2C_1") (pin "2") (pinfunction "2_2") (pintype "unspecified"))
      (node (ref "JST1") (pin "2") (pinfunction "2_2") (pintype "unspecified"))
      (node (ref "JST2") (pin "2") (pinfunction "2_2") (pintype "unspecified"))
      (node (ref "R1") (pin "1") (pinfunction "1_1") (pintype "unspecified"))
      (node (ref "R10") (pin "2") (pinfunction "2_2") (pintype "input"))
      (node (ref "R17") (pin "2") (pinfunction "2_2") (pintype "unspecified"))
      (node (ref "R5") (pin "2") (pinfunction "2_2") (pintype "input"))
      (node (ref "TF1") (pin "4") (pinfunction "VDD_4") (pintype "unspecified"))
      (node (ref "U1") (pin "2") (pinfunction "3V3_2") (pintype "unspecified"))
      (node (ref "U3") (pin "1") (pinfunction "1_1") (pintype "input"))
      (node (ref "U4") (pin "2") (pinfunction "VOUT_2") (pintype "unspecified"))
      (node (ref "U6") (pin "16") (pinfunction "VCC_16") (pintype "unspecified"))
      (node (ref "U6") (pin "4") (pinfunction "V3_4") (pintype "unspecified"))
      (node (ref "U8") (pin "3") (pinfunction "VDD_3") (pintype "unspecified"))
    )
    (net (code "44") (name "VCC_USB") (class "Default")
      (node (ref "BAT-IN") (pin "2") (pinfunction "2_2") (pintype "unspecified"))
      (node (ref "C1") (pin "1") (pinfunction "1_1") (pintype "unspecified"))
      (node (ref "C3") (pin "1") (pinfunction "1_1") (pintype "unspecified"))
      (node (ref "C4") (pin "1") (pinfunction "1_1") (pintype "unspecified"))
      (node (ref "C6") (pin "1") (pinfunction "1_1") (pintype "input"))
      (node (ref "F2") (pin "1") (pinfunction "1_1") (pintype "unspecified"))
      (node (ref "R13") (pin "2") (pinfunction "2_2") (pintype "unspecified"))
      (node (ref "R7") (pin "2") (pinfunction "2_2") (pintype "unspecified"))
      (node (ref "R8") (pin "1") (pinfunction "1_1") (pintype "input"))
      (node (ref "RE") (pin "1") (pinfunction "1_1") (pintype "unspecified"))
      (node (ref "TPS565201DDCR") (pin "3") (pinfunction "VIN_3") (pintype "unspecified"))
    )
    (net (code "45") (name "a") (class "Default")
      (node (ref "DB1") (pin "5") (pinfunction "A_5") (pintype "unspecified"))
      (node (ref "U1") (pin "10") (pinfunction "IO17_10") (pintype "unspecified"))
    )
    (net (code "46") (name "b") (class "Default")
      (node (ref "DB1") (pin "12") (pinfunction "B_12") (pintype "unspecified"))
      (node (ref "U1") (pin "9") (pinfunction "IO16_9") (pintype "unspecified"))
    )
    (net (code "47") (name "b1") (class "Default")
      (node (ref "DB1") (pin "2") (pinfunction "B1_2") (pintype "unspecified"))
      (node (ref "U1") (pin "18") (pinfunction "IO10_18") (pintype "unspecified"))
    )
    (net (code "48") (name "b2") (class "Default")
      (node (ref "DB1") (pin "4") (pinfunction "B2_4") (pintype "unspecified"))
      (node (ref "U1") (pin "11") (pinfunction "IO18_11") (pintype "unspecified"))
    )
    (net (code "49") (name "button") (class "Default")
      (node (ref "R17") (pin "1") (pinfunction "1_1") (pintype "unspecified"))
      (node (ref "U1") (pin "32") (pinfunction "IO39_32") (pintype "unspecified"))
      (node (ref "U15") (pin "3") (pinfunction "3_3") (pintype "unspecified"))
      (node (ref "U15") (pin "4") (pinfunction "4_4") (pintype "unspecified"))
    )
    (net (code "50") (name "buzz") (class "Default")
      (node (ref "BUZZER") (pin "1") (pinfunction "1_1") (pintype "unspecified"))
      (node (ref "U1") (pin "33") (pinfunction "IO40_33") (pintype "unspecified"))
    )
    (net (code "51") (name "c") (class "Default")
      (node (ref "DB1") (pin "6") (pinfunction "C_6") (pintype "unspecified"))
      (node (ref "U1") (pin "8") (pinfunction "IO15_8") (pintype "unspecified"))
    )
    (net (code "52") (name "clk") (class "Default")
      (node (ref "DB1") (pin "7") (pinfunction "CLK_7") (pintype "unspecified"))
      (node (ref "U1") (pin "6") (pinfunction "IO6_6") (pintype "unspecified"))
    )
    (net (code "53") (name "d") (class "Default")
      (node (ref "DB1") (pin "11") (pinfunction "D_11") (pintype "unspecified"))
      (node (ref "U1") (pin "7") (pinfunction "IO7_7") (pintype "unspecified"))
    )
    (net (code "54") (name "g1") (class "Default")
      (node (ref "DB1") (pin "16") (pinfunction "G1_16") (pintype "unspecified"))
      (node (ref "U1") (pin "19") (pinfunction "IO11_19") (pintype "unspecified"))
    )
    (net (code "55") (name "g2") (class "Default")
      (node (ref "DB1") (pin "14") (pinfunction "G2_14") (pintype "unspecified"))
      (node (ref "U1") (pin "13") (pinfunction "IO19_13") (pintype "unspecified"))
    )
    (net (code "56") (name "lat") (class "Default")
      (node (ref "DB1") (pin "10") (pinfunction "LAT_10") (pintype "unspecified"))
      (node (ref "U1") (pin "5") (pinfunction "IO5_5") (pintype "unspecified"))
    )
    (net (code "57") (name "led_0_1") (class "Default")
      (node (ref "D10") (pin "1") (pinfunction "C_1") (pintype "unspecified"))
      (node (ref "LED1") (pin "2") (pinfunction "2_2") (pintype "unspecified"))
      (node (ref "U1") (pin "34") (pinfunction "IO41_34") (pintype "unspecified"))
    )
    (net (code "58") (name "led_0_2") (class "Default")
      (node (ref "D1") (pin "1") (pinfunction "C_1") (pintype "unspecified"))
      (node (ref "LED2") (pin "2") (pinfunction "2_2") (pintype "unspecified"))
      (node (ref "U1") (pin "35") (pinfunction "IO42_35") (pintype "unspecified"))
    )
    (net (code "59") (name "oe") (class "Default")
      (node (ref "DB1") (pin "8") (pinfunction "OE_8") (pintype "unspecified"))
      (node (ref "U1") (pin "4") (pinfunction "IO4_4") (pintype "unspecified"))
    )
    (net (code "60") (name "r1") (class "Default")
      (node (ref "DB1") (pin "1") (pinfunction "R1_1") (pintype "unspecified"))
      (node (ref "U1") (pin "20") (pinfunction "IO12_20") (pintype "unspecified"))
    )
    (net (code "61") (name "r2") (class "Default")
      (node (ref "DB1") (pin "3") (pinfunction "R2_3") (pintype "unspecified"))
      (node (ref "U1") (pin "14") (pinfunction "IO20_14") (pintype "unspecified"))
    )
    (net (code "62") (name "strapping46") (class "Default")
      (node (ref "R2") (pin "1") (pinfunction "1_1") (pintype "unspecified"))
      (node (ref "U1") (pin "16") (pinfunction "IO46_16") (pintype "unspecified"))
    )
    (net (code "63") (name "unconnected-(BUZZER-Pad3)") (class "Default")
      (node (ref "BUZZER") (pin "3") (pinfunction "3_3") (pintype "unspecified+no_connect"))
    )
    (net (code "64") (name "unconnected-(BUZZER-Pad4)") (class "Default")
      (node (ref "BUZZER") (pin "4") (pinfunction "4_4") (pintype "unspecified+no_connect"))
    )
    (net (code "65") (name "unconnected-(TF1-CD-Pad9)") (class "Default")
      (node (ref "TF1") (pin "9") (pinfunction "CD_9") (pintype "unspecified+no_connect"))
    )
    (net (code "66") (name "unconnected-(TF1-DAT1-Pad8)") (class "Default")
      (node (ref "TF1") (pin "8") (pinfunction "DAT1_8") (pintype "unspecified+no_connect"))
    )
    (net (code "67") (name "unconnected-(TF1-DAT2-Pad1)") (class "Default")
      (node (ref "TF1") (pin "1") (pinfunction "DAT2_1") (pintype "unspecified+no_connect"))
    )
    (net (code "68") (name "unconnected-(U1-IO35-Pad28)") (class "Default")
      (node (ref "U1") (pin "28") (pinfunction "IO35_28") (pintype "unspecified+no_connect"))
    )
    (net (code "69") (name "unconnected-(U1-IO36-Pad29)") (class "Default")
      (node (ref "U1") (pin "29") (pinfunction "IO36_29") (pintype "unspecified+no_connect"))
    )
    (net (code "70") (name "unconnected-(U1-IO37-Pad30)") (class "Default")
      (node (ref "U1") (pin "30") (pinfunction "IO37_30") (pintype "unspecified+no_connect"))
    )
    (net (code "71") (name "unconnected-(U1-IO45-Pad26)") (class "Default")
      (node (ref "U1") (pin "26") (pinfunction "IO45_26") (pintype "unspecified+no_connect"))
    )
    (net (code "72") (name "unconnected-(U2-PG-Pad10)") (class "Default")
      (node (ref "U2") (pin "10") (pinfunction "PG_10") (pintype "unspecified"))
    )
    (net (code "73") (name "unconnected-(U6-CTS#-Pad9)") (class "Default")
      (node (ref "U6") (pin "9") (pinfunction "CTS#_9") (pintype "unspecified+no_connect"))
    )
    (net (code "74") (name "unconnected-(U6-DCD#-Pad12)") (class "Default")
      (node (ref "U6") (pin "12") (pinfunction "DCD#_12") (pintype "unspecified+no_connect"))
    )
    (net (code "75") (name "unconnected-(U6-DSR#-Pad10)") (class "Default")
      (node (ref "U6") (pin "10") (pinfunction "DSR#_10") (pintype "unspecified+no_connect"))
    )
    (net (code "76") (name "unconnected-(U6-NC.-Pad7)") (class "Default")
      (node (ref "U6") (pin "7") (pinfunction "NC._7") (pintype "unspecified+no_connect"))
    )
    (net (code "77") (name "unconnected-(U6-OUT#-Pad8)") (class "Default")
      (node (ref "U6") (pin "8") (pinfunction "OUT#_8") (pintype "unspecified+no_connect"))
    )
    (net (code "78") (name "unconnected-(U6-R232-Pad15)") (class "Default")
      (node (ref "U6") (pin "15") (pinfunction "R232_15") (pintype "unspecified+no_connect"))
    )
    (net (code "79") (name "unconnected-(U6-RI#-Pad11)") (class "Default")
      (node (ref "U6") (pin "11") (pinfunction "RI#_11") (pintype "unspecified+no_connect"))
    )
    (net (code "80") (name "unconnected-(USB3-ID-Pad4)") (class "Default")
      (node (ref "USB3") (pin "4") (pinfunction "ID_4") (pintype "unspecified+no_connect"))
    )
  )
)
